# Sheet_1.net
KiCad netlist of a schematic drawn in Altium Designer
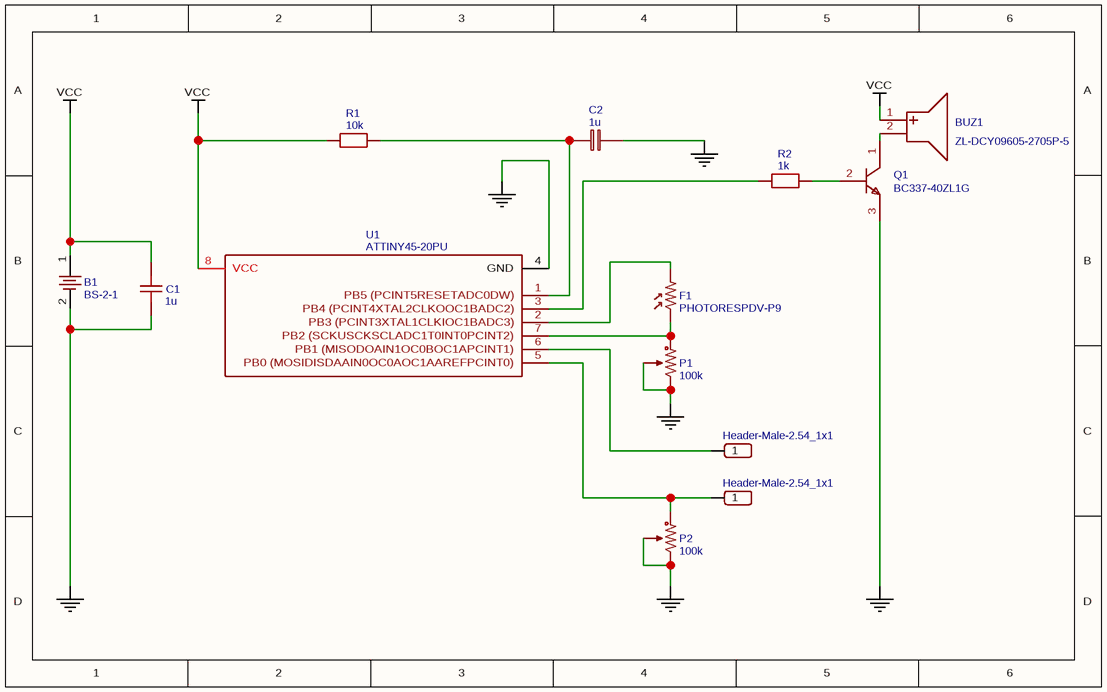
[diagram p0: Sheet_1.schdoc]

(export (version "E")
  (design (tool "Eeschema 10.0.6"))
  (components
    (comp (ref "B1")
      (value "BS-2-1")
      (fields (field (name "BOM_SUPPLIER PART") "C70376"))
      (libsource (lib "altium-import") (part "root_3_BS-2-1_"))
    )
    (comp (ref "BUZ1")
      (value "ZL-DCY09605-2705P-5")
      (fields (field (name "BOM_SUPPLIER PART") "C194534") (field (name "CONTRIBUTOR") "LCSC"))
      (libsource (lib "altium-import") (part "root_2_ZL-DCY09605-2705P-5_"))
    )
    (comp (ref "C1")
      (value "1u")
      (fields (field (name "BOM_MANUFACTURER PART") "?"))
      (libsource (lib "altium-import") (part "root_0_1u_"))
    )
    (comp (ref "C2")
      (value "1u")
      (fields (field (name "BOM_MANUFACTURER PART") "?"))
      (libsource (lib "altium-import") (part "root_1_1u_"))
    )
    (comp (ref "CONN1")
      (value "Header-Male-2.54_1x1")
      (fields (field (name "BOM_SUPPLIER PART") "C81276"))
      (libsource (lib "altium-import") (part "root_0_Header-Male-2.54_1x1_"))
    )
    (comp (ref "CONN2")
      (value "Header-Male-2.54_1x1")
      (fields (field (name "BOM_SUPPLIER PART") "C81276"))
      (libsource (lib "altium-import") (part "root_0_Header-Male-2.54_1x1_"))
    )
    (comp (ref "F1")
      (value "PHOTORESPDV-P9")
      (fields (field (name "BOM_MANUFACTURER PART") "?"))
      (libsource (lib "altium-import") (part "root_1_PHOTORESPDV-P9_"))
    )
    (comp (ref "P1")
      (value "100k")
      (fields (field (name "BOM_MANUFACTURER PART") "?"))
      (libsource (lib "altium-import") (part "root_1_100k_"))
    )
    (comp (ref "P2")
      (value "100k")
      (fields (field (name "BOM_MANUFACTURER PART") "?"))
      (libsource (lib "altium-import") (part "root_1_100k_"))
    )
    (comp (ref "Q1")
      (value "BC337-40ZL1G")
      (description "Amplifier Transistor, NPN Silicon, 3-Pin TO-92, Pb-Free, Ammo Box")
      (fields (field (name "BOM_MANUFACTURER PART") "?"))
      (libsource (lib "altium-import") (part "root_0_BC337-40ZL1G_"))
    )
    (comp (ref "R1")
      (value "10k")
      (fields (field (name "BOM_MANUFACTURER PART") "?"))
      (libsource (lib "altium-import") (part "root_0_10k_"))
    )
    (comp (ref "R2")
      (value "1k")
      (fields (field (name "BOM_MANUFACTURER PART") "?"))
      (libsource (lib "altium-import") (part "root_0_1k_"))
    )
    (comp (ref "U1")
      (value "ATTINY45-20PU")
      (fields (field (name "BOM_SUPPLIER PART") "C152181") (field (name "CONTRIBUTOR") "LCSC"))
      (libsource (lib "altium-import") (part "root_2_ATTINY45-20PU_"))
    )
  )
  (nets
    (net (code "1") (name "GND") (class "Default")
      (node (ref "B1") (pin "2") (pinfunction "2_2") (pintype "passive"))
      (node (ref "C1") (pin "1") (pinfunction "1_1") (pintype "passive"))
      (node (ref "C2") (pin "2") (pinfunction "2_2") (pintype "passive"))
      (node (ref "P1") (pin "1") (pinfunction "1_1") (pintype "passive"))
      (node (ref "P1") (pin "2") (pinfunction "3_2") (pintype "passive"))
      (node (ref "P2") (pin "1") (pinfunction "1_1") (pintype "passive"))
      (node (ref "P2") (pin "2") (pinfunction "3_2") (pintype "passive"))
      (node (ref "Q1") (pin "3") (pinfunction "E_3") (pintype "passive"))
      (node (ref "U1") (pin "4") (pinfunction "GND_4") (pintype "passive"))
    )
    (net (code "2") (name "Net-(BUZ1--)") (class "Default")
      (node (ref "BUZ1") (pin "2") (pinfunction "-_2") (pintype "passive"))
      (node (ref "Q1") (pin "1") (pinfunction "C_1") (pintype "passive"))
    )
    (net (code "3") (name "Net-(P1-2)") (class "Default")
      (node (ref "F1") (pin "1") (pinfunction "1_1") (pintype "passive"))
      (node (ref "P1") (pin "3") (pinfunction "2_3") (pintype "passive"))
      (node (ref "U1") (pin "7") (pinfunction "PB2_(SCKUSCKSCLADC1T0INT0PCINT2)_7") (pintype "passive"))
    )
    (net (code "4") (name "Net-(P2-2)") (class "Default")
      (node (ref "CONN2") (pin "1") (pinfunction "1_1") (pintype "passive"))
      (node (ref "P2") (pin "3") (pinfunction "2_3") (pintype "passive"))
      (node (ref "U1") (pin "5") (pinfunction "PB0_(MOSIDISDAAIN0OC0AOC1AAREFPCINT0)_5") (pintype "passive"))
    )
    (net (code "5") (name "Net-(Q1-B)") (class "Default")
      (node (ref "Q1") (pin "2") (pinfunction "B_2") (pintype "passive"))
      (node (ref "R2") (pin "2") (pinfunction "2_2") (pintype "passive"))
    )
    (net (code "6") (name "Net-(U1-PB1_(MISODOAIN1OC0BOC1APCINT1))") (class "Default")
      (node (ref "CONN1") (pin "1") (pinfunction "1_1") (pintype "passive"))
      (node (ref "U1") (pin "6") (pinfunction "PB1_(MISODOAIN1OC0BOC1APCINT1)_6") (pintype "passive"))
    )
    (net (code "7") (name "Net-(U1-PB3_(PCINT3XTAL1CLKIOC1BADC3))") (class "Default")
      (node (ref "F1") (pin "2") (pinfunction "2_2") (pintype "passive"))
      (node (ref "U1") (pin "2") (pinfunction "PB3_(PCINT3XTAL1CLKIOC1BADC3)_2") (pintype "passive"))
    )
    (net (code "8") (name "Net-(U1-PB4_(PCINT4XTAL2CLKOOC1BADC2))") (class "Default")
      (node (ref "R2") (pin "1") (pinfunction "1_1") (pintype "passive"))
      (node (ref "U1") (pin "3") (pinfunction "PB4_(PCINT4XTAL2CLKOOC1BADC2)_3") (pintype "passive"))
    )
    (net (code "9") (name "Net-(U1-PB5_(PCINT5RESETADC0DW))") (class "Default")
      (node (ref "C2") (pin "1") (pinfunction "1_1") (pintype "passive"))
      (node (ref "R1") (pin "2") (pinfunction "2_2") (pintype "passive"))
      (node (ref "U1") (pin "1") (pinfunction "PB5_(PCINT5RESETADC0DW)_1") (pintype "passive"))
    )
    (net (code "10") (name "VCC") (class "Default")
      (node (ref "B1") (pin "1") (pinfunction "1_1") (pintype "passive"))
      (node (ref "BUZ1") (pin "1") (pinfunction "+_1") (pintype "passive"))
      (node (ref "C1") (pin "2") (pinfunction "2_2") (pintype "passive"))
      (node (ref "R1") (pin "1") (pinfunction "1_1") (pintype "passive"))
      (node (ref "U1") (pin "8") (pinfunction "VCC_8") (pintype "passive"))
    )
  )
)
